# kossel_mini_extruder.net
KiCad netlist of a schematic drawn in EAGLE
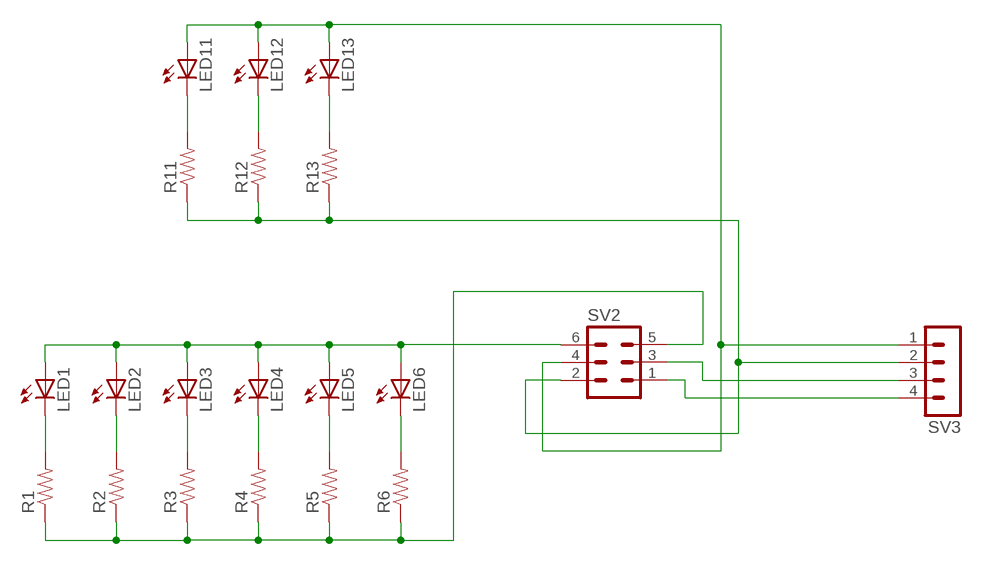
[diagram p0: schematic, sheet 1]

(export (version "E")
  (design (tool "Eeschema 10.0.6"))
  (components
    (comp (ref "LED1")
      (value "LED0805")
      (footprint "eagle-import:CHIPLED_0805")
      (libsource (lib "eagle-import") (part "LED0805"))
    )
    (comp (ref "LED2")
      (value "LED0805")
      (footprint "eagle-import:CHIPLED_0805")
      (libsource (lib "eagle-import") (part "LED0805"))
    )
    (comp (ref "LED3")
      (value "LED0805")
      (footprint "eagle-import:CHIPLED_0805")
      (libsource (lib "eagle-import") (part "LED0805"))
    )
    (comp (ref "LED4")
      (value "LED0805")
      (footprint "eagle-import:CHIPLED_0805")
      (libsource (lib "eagle-import") (part "LED0805"))
    )
    (comp (ref "LED5")
      (value "LED0805")
      (footprint "eagle-import:CHIPLED_0805")
      (libsource (lib "eagle-import") (part "LED0805"))
    )
    (comp (ref "LED6")
      (value "LED0805")
      (footprint "eagle-import:CHIPLED_0805")
      (libsource (lib "eagle-import") (part "LED0805"))
    )
    (comp (ref "LED11")
      (value "LED0805")
      (footprint "eagle-import:CHIPLED_0805")
      (libsource (lib "eagle-import") (part "LED0805"))
    )
    (comp (ref "LED12")
      (value "LED0805")
      (footprint "eagle-import:CHIPLED_0805")
      (libsource (lib "eagle-import") (part "LED0805"))
    )
    (comp (ref "LED13")
      (value "LED0805")
      (footprint "eagle-import:CHIPLED_0805")
      (libsource (lib "eagle-import") (part "LED0805"))
    )
    (comp (ref "R1")
      (value "RESISTOR0805-RES")
      (footprint "eagle-import:0805")
      (libsource (lib "eagle-import") (part "RESISTOR0805-RES"))
    )
    (comp (ref "R2")
      (value "RESISTOR0805-RES")
      (footprint "eagle-import:0805")
      (libsource (lib "eagle-import") (part "RESISTOR0805-RES"))
    )
    (comp (ref "R3")
      (value "RESISTOR0805-RES")
      (footprint "eagle-import:0805")
      (libsource (lib "eagle-import") (part "RESISTOR0805-RES"))
    )
    (comp (ref "R4")
      (value "RESISTOR0805-RES")
      (footprint "eagle-import:0805")
      (libsource (lib "eagle-import") (part "RESISTOR0805-RES"))
    )
    (comp (ref "R5")
      (value "RESISTOR0805-RES")
      (footprint "eagle-import:0805")
      (libsource (lib "eagle-import") (part "RESISTOR0805-RES"))
    )
    (comp (ref "R6")
      (value "RESISTOR0805-RES")
      (footprint "eagle-import:0805")
      (libsource (lib "eagle-import") (part "RESISTOR0805-RES"))
    )
    (comp (ref "R11")
      (value "RESISTOR0805-RES")
      (footprint "eagle-import:0805")
      (libsource (lib "eagle-import") (part "RESISTOR0805-RES"))
    )
    (comp (ref "R12")
      (value "RESISTOR0805-RES")
      (footprint "eagle-import:0805")
      (libsource (lib "eagle-import") (part "RESISTOR0805-RES"))
    )
    (comp (ref "R13")
      (value "RESISTOR0805-RES")
      (footprint "eagle-import:0805")
      (libsource (lib "eagle-import") (part "RESISTOR0805-RES"))
    )
    (comp (ref "SV2")
      (value "MA03-2")
      (footprint "eagle-import:MA03-2")
      (libsource (lib "eagle-import") (part "MA03-2"))
    )
    (comp (ref "SV3")
      (value "MA04-1")
      (footprint "eagle-import:MA04-1")
      (libsource (lib "eagle-import") (part "MA04-1"))
    )
  )
  (nets
    (net (code "1") (name "Net-(LED1-PadA)") (class "Default")
      (node (ref "LED1") (pin "A") (pinfunction "A_A") (pintype "passive"))
      (node (ref "LED2") (pin "A") (pinfunction "A_A") (pintype "passive"))
      (node (ref "LED3") (pin "A") (pinfunction "A_A") (pintype "passive"))
      (node (ref "LED4") (pin "A") (pinfunction "A_A") (pintype "passive"))
      (node (ref "LED5") (pin "A") (pinfunction "A_A") (pintype "passive"))
      (node (ref "LED6") (pin "A") (pinfunction "A_A") (pintype "passive"))
      (node (ref "SV2") (pin "6") (pinfunction "6_6") (pintype "passive"))
    )
    (net (code "2") (name "Net-(LED1-PadC)") (class "Default")
      (node (ref "LED1") (pin "C") (pinfunction "C_C") (pintype "passive"))
      (node (ref "R1") (pin "2") (pinfunction "2_2") (pintype "passive"))
    )
    (net (code "3") (name "Net-(LED2-PadC)") (class "Default")
      (node (ref "LED2") (pin "C") (pinfunction "C_C") (pintype "passive"))
      (node (ref "R2") (pin "2") (pinfunction "2_2") (pintype "passive"))
    )
    (net (code "4") (name "Net-(LED3-PadC)") (class "Default")
      (node (ref "LED3") (pin "C") (pinfunction "C_C") (pintype "passive"))
      (node (ref "R3") (pin "2") (pinfunction "2_2") (pintype "passive"))
    )
    (net (code "5") (name "Net-(LED4-PadC)") (class "Default")
      (node (ref "LED4") (pin "C") (pinfunction "C_C") (pintype "passive"))
      (node (ref "R4") (pin "2") (pinfunction "2_2") (pintype "passive"))
    )
    (net (code "6") (name "Net-(LED5-PadC)") (class "Default")
      (node (ref "LED5") (pin "C") (pinfunction "C_C") (pintype "passive"))
      (node (ref "R5") (pin "2") (pinfunction "2_2") (pintype "passive"))
    )
    (net (code "7") (name "Net-(LED6-PadC)") (class "Default")
      (node (ref "LED6") (pin "C") (pinfunction "C_C") (pintype "passive"))
      (node (ref "R6") (pin "2") (pinfunction "2_2") (pintype "passive"))
    )
    (net (code "8") (name "Net-(LED11-PadA)") (class "Default")
      (node (ref "LED11") (pin "A") (pinfunction "A_A") (pintype "passive"))
      (node (ref "LED12") (pin "A") (pinfunction "A_A") (pintype "passive"))
      (node (ref "LED13") (pin "A") (pinfunction "A_A") (pintype "passive"))
      (node (ref "SV2") (pin "4") (pinfunction "4_4") (pintype "passive"))
      (node (ref "SV3") (pin "1") (pinfunction "1_1") (pintype "passive"))
    )
    (net (code "9") (name "Net-(LED11-PadC)") (class "Default")
      (node (ref "LED11") (pin "C") (pinfunction "C_C") (pintype "passive"))
      (node (ref "R11") (pin "2") (pinfunction "2_2") (pintype "passive"))
    )
    (net (code "10") (name "Net-(LED12-PadC)") (class "Default")
      (node (ref "LED12") (pin "C") (pinfunction "C_C") (pintype "passive"))
      (node (ref "R12") (pin "2") (pinfunction "2_2") (pintype "passive"))
    )
    (net (code "11") (name "Net-(LED13-PadC)") (class "Default")
      (node (ref "LED13") (pin "C") (pinfunction "C_C") (pintype "passive"))
      (node (ref "R13") (pin "2") (pinfunction "2_2") (pintype "passive"))
    )
    (net (code "12") (name "Net-(R1-Pad1)") (class "Default")
      (node (ref "R1") (pin "1") (pinfunction "1_1") (pintype "passive"))
      (node (ref "R2") (pin "1") (pinfunction "1_1") (pintype "passive"))
      (node (ref "R3") (pin "1") (pinfunction "1_1") (pintype "passive"))
      (node (ref "R4") (pin "1") (pinfunction "1_1") (pintype "passive"))
      (node (ref "R5") (pin "1") (pinfunction "1_1") (pintype "passive"))
      (node (ref "R6") (pin "1") (pinfunction "1_1") (pintype "passive"))
      (node (ref "SV2") (pin "5") (pinfunction "5_5") (pintype "passive"))
    )
    (net (code "13") (name "Net-(R11-Pad1)") (class "Default")
      (node (ref "R11") (pin "1") (pinfunction "1_1") (pintype "passive"))
      (node (ref "R12") (pin "1") (pinfunction "1_1") (pintype "passive"))
      (node (ref "R13") (pin "1") (pinfunction "1_1") (pintype "passive"))
      (node (ref "SV2") (pin "2") (pinfunction "2_2") (pintype "passive"))
      (node (ref "SV3") (pin "2") (pinfunction "2_2") (pintype "passive"))
    )
    (net (code "14") (name "Net-(SV2-Pad1)") (class "Default")
      (node (ref "SV2") (pin "1") (pinfunction "1_1") (pintype "passive"))
      (node (ref "SV3") (pin "4") (pinfunction "4_4") (pintype "passive"))
    )
    (net (code "15") (name "Net-(SV2-Pad3)") (class "Default")
      (node (ref "SV2") (pin "3") (pinfunction "3_3") (pintype "passive"))
      (node (ref "SV3") (pin "3") (pinfunction "3_3") (pintype "passive"))
    )
  )
)
